# n24_att.net
KiCad netlist of a schematic drawn in Altium Designer
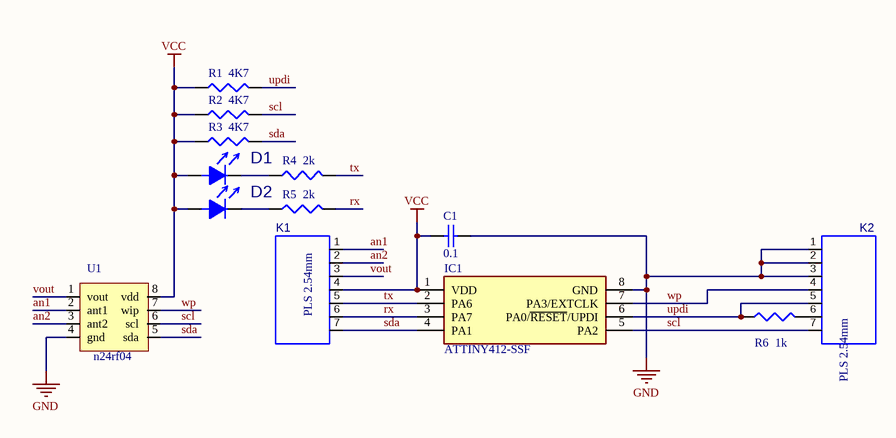
[diagram p0: n24_att.SchDoc]

(export (version "E")
  (design (tool "Eeschema 10.0.6"))
  (components
    (comp (ref "C1")
      (value "0.1")
      (footprint "SM0805")
      (description "Capacitor")
      (fields (field (name "Comment") "cap0805") (field (name "PUBLISHER") "Altium Limited"))
      (libsource (lib "alt2017") (part "cap0805"))
    )
    (comp (ref "D1")
      (value "LIGHT_SM0805")
      (footprint "SM0805_diode")
      (libsource (lib "alt2017") (part "LIGHT_SM0805"))
    )
    (comp (ref "D2")
      (value "LIGHT_SM0805")
      (footprint "SM0805_diode")
      (libsource (lib "alt2017") (part "LIGHT_SM0805"))
    )
    (comp (ref "IC1")
      (value "ATTINY412-SSF")
      (footprint "SamacSys:SOIC127P600X175-8N")
      (description "Integrated Circuit")
      (fields (field (name "MOUSER PART NUMBER") "579-ATTINY412-SSF"))
      (libsource (lib "*") (part "ATTINY412-SSF"))
    )
    (comp (ref "K1")
      (value "7_PLS_2.54mm")
      (footprint "7_PLS_2.54")
      (description "7 pin vertical 2.54mm")
      (libsource (lib "alt2017") (part "7_PLS_2.54mm"))
    )
    (comp (ref "K2")
      (value "7_PLS_2.54mm")
      (footprint "7_PLS_2.54")
      (description "7 pin vertical 2.54mm")
      (libsource (lib "alt2017") (part "7_PLS_2.54mm"))
    )
    (comp (ref "R1")
      (value "4K7")
      (footprint "SM0805")
      (description "Resistor")
      (fields (field (name "Comment") "res0805") (field (name "PUBLISHER") "Altium Limited"))
      (libsource (lib "alt2017") (part "res0805"))
    )
    (comp (ref "R2")
      (value "4K7")
      (footprint "SM0805")
      (description "Resistor")
      (fields (field (name "Comment") "res0805") (field (name "PUBLISHER") "Altium Limited"))
      (libsource (lib "alt2017") (part "res0805"))
    )
    (comp (ref "R3")
      (value "4K7")
      (footprint "SM0805")
      (description "Resistor")
      (fields (field (name "Comment") "res0805") (field (name "PUBLISHER") "Altium Limited"))
      (libsource (lib "alt2017") (part "res0805"))
    )
    (comp (ref "R4")
      (value "2k")
      (footprint "SM0805")
      (description "Resistor")
      (fields (field (name "Comment") "res0805") (field (name "PUBLISHER") "Altium Limited"))
      (libsource (lib "alt2017") (part "res0805"))
    )
    (comp (ref "R5")
      (value "2k")
      (footprint "SM0805")
      (description "Resistor")
      (fields (field (name "Comment") "res0805") (field (name "PUBLISHER") "Altium Limited"))
      (libsource (lib "alt2017") (part "res0805"))
    )
    (comp (ref "R6")
      (value "1k")
      (footprint "SM0805")
      (description "Resistor")
      (fields (field (name "Comment") "res0805") (field (name "PUBLISHER") "Altium Limited"))
      (libsource (lib "alt2017") (part "res0805"))
    )
    (comp (ref "U1")
      (value "n24rf04")
      (footprint "SO8_L")
      (description "eeprom & nfc tag")
      (libsource (lib "alt2017") (part "n24rf04"))
    )
  )
  (nets
    (net (code "1") (name "/an1") (class "Default")
      (node (ref "K1") (pin "1") (pinfunction "1_1") (pintype "passive"))
      (node (ref "U1") (pin "2") (pinfunction "ant1_2") (pintype "passive"))
    )
    (net (code "2") (name "/an2") (class "Default")
      (node (ref "K1") (pin "2") (pinfunction "2_2") (pintype "passive"))
      (node (ref "U1") (pin "3") (pinfunction "ant2_3") (pintype "passive"))
    )
    (net (code "3") (name "/rx") (class "Default")
      (node (ref "IC1") (pin "3") (pinfunction "PA7_3") (pintype "passive"))
      (node (ref "K1") (pin "6") (pinfunction "6_6") (pintype "passive"))
      (node (ref "R5") (pin "2") (pinfunction "2_2") (pintype "passive"))
    )
    (net (code "4") (name "/scl") (class "Default")
      (node (ref "IC1") (pin "5") (pinfunction "PA2_5") (pintype "passive"))
      (node (ref "K2") (pin "7") (pinfunction "7_7") (pintype "passive"))
      (node (ref "R2") (pin "2") (pinfunction "2_2") (pintype "passive"))
      (node (ref "U1") (pin "6") (pinfunction "scl_6") (pintype "passive"))
    )
    (net (code "5") (name "/sda") (class "Default")
      (node (ref "IC1") (pin "4") (pinfunction "PA1_4") (pintype "passive"))
      (node (ref "K1") (pin "7") (pinfunction "7_7") (pintype "passive"))
      (node (ref "R3") (pin "2") (pinfunction "2_2") (pintype "passive"))
      (node (ref "U1") (pin "5") (pinfunction "sda_5") (pintype "passive"))
    )
    (net (code "6") (name "/tx") (class "Default")
      (node (ref "IC1") (pin "2") (pinfunction "PA6_2") (pintype "passive"))
      (node (ref "K1") (pin "5") (pinfunction "5_5") (pintype "passive"))
      (node (ref "R4") (pin "2") (pinfunction "2_2") (pintype "passive"))
    )
    (net (code "7") (name "/updi") (class "Default")
      (node (ref "IC1") (pin "6") (pinfunction "PA0/~{RESET}/UPDI_6") (pintype "passive"))
      (node (ref "K2") (pin "5") (pinfunction "5_5") (pintype "passive"))
      (node (ref "R1") (pin "2") (pinfunction "2_2") (pintype "passive"))
      (node (ref "R6") (pin "1") (pinfunction "1_1") (pintype "passive"))
    )
    (net (code "8") (name "/vout") (class "Default")
      (node (ref "K1") (pin "3") (pinfunction "3_3") (pintype "passive"))
      (node (ref "U1") (pin "1") (pinfunction "vout_1") (pintype "passive"))
    )
    (net (code "9") (name "/wp") (class "Default")
      (node (ref "IC1") (pin "7") (pinfunction "PA3/EXTCLK_7") (pintype "passive"))
      (node (ref "K2") (pin "4") (pinfunction "4_4") (pintype "passive"))
      (node (ref "U1") (pin "7") (pinfunction "wip_7") (pintype "passive"))
    )
    (net (code "10") (name "GND") (class "Default")
      (node (ref "C1") (pin "2") (pinfunction "2_2") (pintype "passive"))
      (node (ref "IC1") (pin "8") (pinfunction "GND_8") (pintype "passive"))
      (node (ref "K2") (pin "1") (pinfunction "1_1") (pintype "passive"))
      (node (ref "K2") (pin "2") (pinfunction "2_2") (pintype "passive"))
      (node (ref "K2") (pin "3") (pinfunction "3_3") (pintype "passive"))
      (node (ref "U1") (pin "4") (pinfunction "gnd_4") (pintype "passive"))
    )
    (net (code "11") (name "Net-(D1-k)") (class "Default")
      (node (ref "D1") (pin "2") (pinfunction "k_2") (pintype "passive"))
      (node (ref "R4") (pin "1") (pinfunction "1_1") (pintype "passive"))
    )
    (net (code "12") (name "Net-(D2-k)") (class "Default")
      (node (ref "D2") (pin "2") (pinfunction "k_2") (pintype "passive"))
      (node (ref "R5") (pin "1") (pinfunction "1_1") (pintype "passive"))
    )
    (net (code "13") (name "Net-(K2-Pad6)") (class "Default")
      (node (ref "K2") (pin "6") (pinfunction "6_6") (pintype "passive"))
      (node (ref "R6") (pin "2") (pinfunction "2_2") (pintype "passive"))
    )
    (net (code "14") (name "VCC") (class "Default")
      (node (ref "C1") (pin "1") (pinfunction "1_1") (pintype "passive"))
      (node (ref "D1") (pin "1") (pinfunction "a_1") (pintype "passive"))
      (node (ref "D2") (pin "1") (pinfunction "a_1") (pintype "passive"))
      (node (ref "IC1") (pin "1") (pinfunction "VDD_1") (pintype "passive"))
      (node (ref "K1") (pin "4") (pinfunction "4_4") (pintype "passive"))
      (node (ref "R1") (pin "1") (pinfunction "1_1") (pintype "passive"))
      (node (ref "R2") (pin "1") (pinfunction "1_1") (pintype "passive"))
      (node (ref "R3") (pin "1") (pinfunction "1_1") (pintype "passive"))
      (node (ref "U1") (pin "8") (pinfunction "vdd_8") (pintype "passive"))
    )
  )
)
